# smoothieboard-5driver_2.net
KiCad netlist of a schematic drawn in Altium Designer
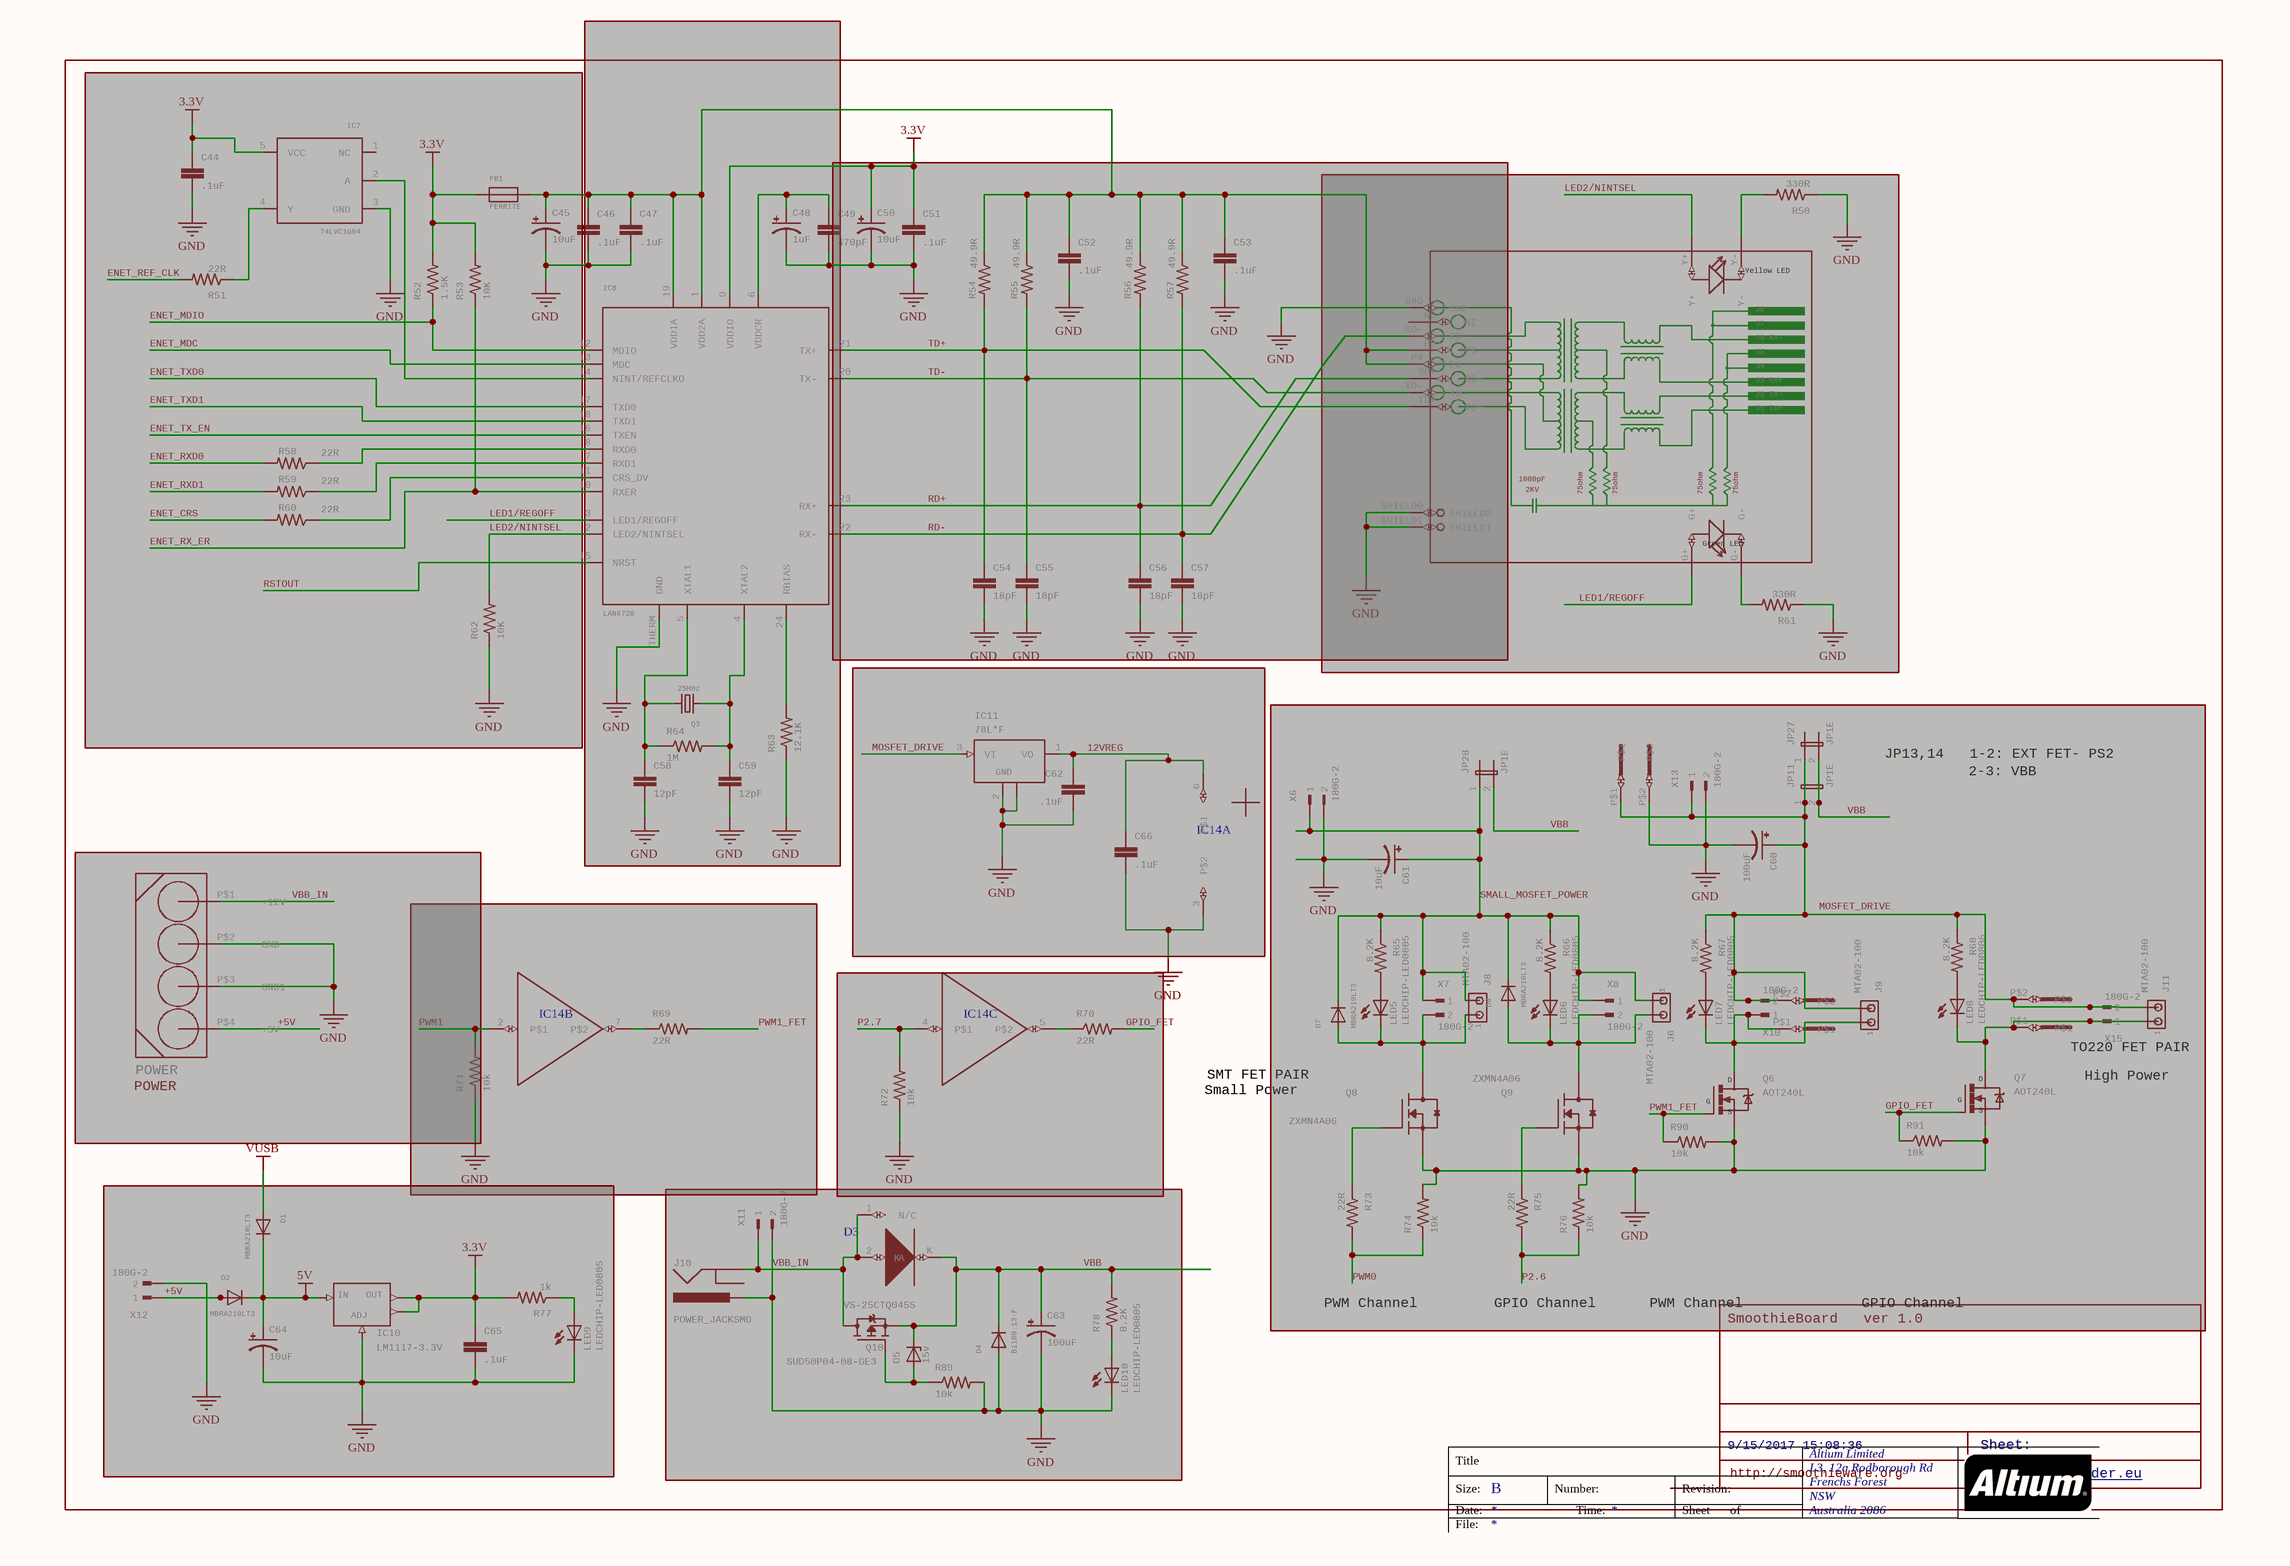
[diagram p0: smoothieboard-5driver_2.SchDoc]

(export (version "E")
  (design (tool "Eeschema 10.0.6"))
  (components
    (comp (ref "C44")
      (value ".1uF")
      (footprint "C0603")
      (description "CAPACITOR, European symbol")
      (libsource (lib "resistor") (part "C-EUC0603"))
    )
    (comp (ref "C45") (value "10uF") (footprint "EIA3216") (libsource (lib "SparkFun") (part "CAP_POL1206")))
    (comp (ref "C46")
      (value ".1uF")
      (footprint "C0603")
      (description "CAPACITOR, European symbol")
      (libsource (lib "resistor") (part "C-EUC0603"))
    )
    (comp (ref "C47")
      (value ".1uF")
      (footprint "C0603")
      (description "CAPACITOR, European symbol")
      (libsource (lib "resistor") (part "C-EUC0603"))
    )
    (comp (ref "C48") (value "1uF") (footprint "EIA3216") (libsource (lib "SparkFun") (part "CAP_POL1206")))
    (comp (ref "C49")
      (value "470pF")
      (footprint "C0603K")
      (description "CAPACITOR, European symbol")
      (libsource (lib "resistor") (part "C-EUC0603K"))
    )
    (comp (ref "C50") (value "10uF") (footprint "EIA3216") (libsource (lib "SparkFun") (part "CAP_POL1206")))
    (comp (ref "C51")
      (value ".1uF")
      (footprint "C0603")
      (description "CAPACITOR, European symbol")
      (libsource (lib "resistor") (part "C-EUC0603"))
    )
    (comp (ref "C52")
      (value ".1uF")
      (footprint "C0603")
      (description "CAPACITOR, European symbol")
      (libsource (lib "resistor") (part "C-EUC0603"))
    )
    (comp (ref "C53")
      (value ".1uF")
      (footprint "C0603")
      (description "CAPACITOR, European symbol")
      (libsource (lib "resistor") (part "C-EUC0603"))
    )
    (comp (ref "C54")
      (value "18pF")
      (footprint "C0603")
      (description "CAPACITOR, European symbol")
      (libsource (lib "resistor") (part "C-EUC0603"))
    )
    (comp (ref "C55")
      (value "18pF")
      (footprint "C0603")
      (description "CAPACITOR, European symbol")
      (libsource (lib "resistor") (part "C-EUC0603"))
    )
    (comp (ref "C56")
      (value "18pF")
      (footprint "C0603")
      (description "CAPACITOR, European symbol")
      (libsource (lib "resistor") (part "C-EUC0603"))
    )
    (comp (ref "C57")
      (value "18pF")
      (footprint "C0603")
      (description "CAPACITOR, European symbol")
      (libsource (lib "resistor") (part "C-EUC0603"))
    )
    (comp (ref "C58")
      (value "12pF")
      (footprint "C0603")
      (description "CAPACITOR, European symbol")
      (libsource (lib "resistor") (part "C-EUC0603"))
    )
    (comp (ref "C59")
      (value "12pF")
      (footprint "C0603")
      (description "CAPACITOR, European symbol")
      (libsource (lib "resistor") (part "C-EUC0603"))
    )
    (comp (ref "C60")
      (value "100uF")
      (footprint "PANASONIC_E")
      (libsource (lib "SparkFun") (part "CAP_POLE"))
    )
    (comp (ref "C61") (value "10uF") (footprint "EIA3216") (libsource (lib "") (part "CAP_POL1206_1")))
    (comp (ref "C62")
      (value ".1uF")
      (footprint "C0603")
      (description "CAPACITOR, European symbol")
      (libsource (lib "") (part "C-EUC0603_1"))
    )
    (comp (ref "C63")
      (value "100uF")
      (footprint "PANASONIC_E")
      (libsource (lib "SparkFun-Capacitors") (part "CAP_POLE"))
    )
    (comp (ref "C64") (value "10uF") (footprint "EIA3216") (libsource (lib "SparkFun") (part "CAP_POL1206")))
    (comp (ref "C65")
      (value ".1uF")
      (footprint "C0603")
      (description "CAPACITOR, European symbol")
      (libsource (lib "resistor") (part "C-EUC0603"))
    )
    (comp (ref "C66")
      (value ".1uF")
      (footprint "C0603")
      (description "CAPACITOR, European symbol")
      (libsource (lib "resistor") (part "C-EUC0603"))
    )
    (comp (ref "D1")
      (value "MBRA210LT3")
      (footprint "SMADIODE")
      (libsource (lib "microbuilder") (part "DIODESMA"))
    )
    (comp (ref "D2")
      (value "MBRA210LT3")
      (footprint "SMADIODE")
      (libsource (lib "microbuilder") (part "DIODESMA"))
    )
    (comp (ref "D3")
      (value "VS-25CTQ045S")
      (footprint "TO263AB")
      (fields (field (name "LIBRARYNAME") "Geos"))
      (libsource (lib "Geos") (part "ETH1506S"))
    )
    (comp (ref "D4")
      (value "B1100-13-F")
      (footprint "SMADIODE")
      (libsource (lib "microbuilder") (part "DIODESMA"))
    )
    (comp (ref "D5")
      (value "15v")
      (footprint "SMB")
      (description "Z-Diode")
      (libsource (lib "diode") (part "ZENER-DIODESMB"))
    )
    (comp (ref "D7")
      (value "MBRA210LT3")
      (footprint "SMADIODE")
      (libsource (lib "microbuilder") (part "DIODESMA"))
    )
    (comp (ref "D8")
      (value "MBRA210LT3")
      (footprint "SMADIODE")
      (libsource (lib "microbuilder") (part "DIODESMA"))
    )
    (comp (ref "FB1") (value "FERRITE") (footprint "0603") (libsource (lib "microbuilder") (part "FERRITE")))
    (comp (ref "IC7")
      (value "74LVC1G04")
      (footprint "SOT23-5")
      (description "74LVC1G04 - Single Inverter Gate    SOT23-5 SN74LVC1G04DBVR - Digikey: 296-11599-1-ND")
      (libsource (lib "microbuilder") (part "74LVC1G04"))
    )
    (comp (ref "IC8")
      (value "LAN8720")
      (footprint "QFN24_4MM")
      (description "LAN8720A 10/100 Ethernet PHY   Mouser: 886-LAN8720AI-CP")
      (libsource (lib "microbuilder") (part "LAN8720"))
    )
    (comp (ref "IC10")
      (value "LM1117-3.3V")
      (footprint "SOT223")
      (fields (field (name "ADJ") "ADJ") (field (name "IN") "IN") (field (name "OUT") "OUT"))
      (libsource (lib "SparkFun") (part "V_REG_LM1117SOT223"))
    )
    (comp (ref "IC11")
      (value "78L*F")
      (footprint "SOT89")
      (fields (field (name "GND") "GND"))
      (libsource (lib "linear") (part "78L*F"))
    )
    (comp (ref "IC14")
      (value "TC4427")
      (footprint "SOIC8")
      (fields (field (name "LIBRARYNAME") "custom_esorensen"))
      (libsource (lib "custom_esorensen") (part "TC4427"))
    )
    (comp (ref "J6")
      (value "MTA02-100")
      (footprint "10X02MTA")
      (description "AMP connector")
      (fields (field (name "1") "1"))
      (libsource (lib "con-amp") (part "MTA02-100"))
    )
    (comp (ref "J8")
      (value "MTA02-100")
      (footprint "10X02MTA")
      (description "AMP connector")
      (fields (field (name "1") "1"))
      (libsource (lib "con-amp") (part "MTA02-100"))
    )
    (comp (ref "J9")
      (value "MTA02-100")
      (footprint "10X02MTA")
      (description "AMP connector")
      (fields (field (name "1") "1"))
      (libsource (lib "con-amp") (part "MTA02-100"))
    )
    (comp (ref "J10")
      (value "POWER_JACKSMD")
      (footprint "POWER_JACK_SMD")
      (libsource (lib "SparkFun") (part "POWER_JACKSMD"))
    )
    (comp (ref "J11")
      (value "MTA02-100")
      (footprint "10X02MTA")
      (description "AMP connector")
      (fields (field (name "1") "1"))
      (libsource (lib "con-amp") (part "MTA02-100"))
    )
    (comp (ref "JP11")
      (value "JP1E")
      (footprint "JP1")
      (description "JUMPER")
      (libsource (lib "jumper") (part "JP1E"))
    )
    (comp (ref "JP27")
      (value "JP1E")
      (footprint "JP1")
      (description "JUMPER")
      (libsource (lib "jumper") (part "JP1E"))
    )
    (comp (ref "JP28")
      (value "JP1E")
      (footprint "JP1")
      (description "JUMPER")
      (libsource (lib "jumper") (part "JP1E"))
    )
    (comp (ref "LED5")
      (value "LEDCHIP-LED0805")
      (footprint "CHIP-LED0805")
      (libsource (lib "led") (part "LEDCHIP-LED0805"))
    )
    (comp (ref "LED6")
      (value "LEDCHIP-LED0805")
      (footprint "CHIP-LED0805")
      (libsource (lib "led") (part "LEDCHIP-LED0805"))
    )
    (comp (ref "LED7")
      (value "LEDCHIP-LED0805")
      (footprint "CHIP-LED0805")
      (libsource (lib "led") (part "LEDCHIP-LED0805"))
    )
    (comp (ref "LED8")
      (value "LEDCHIP-LED0805")
      (footprint "CHIP-LED0805")
      (libsource (lib "led") (part "LEDCHIP-LED0805"))
    )
    (comp (ref "LED9")
      (value "LEDCHIP-LED0805")
      (footprint "CHIP-LED0805")
      (libsource (lib "led") (part "LEDCHIP-LED0805"))
    )
    (comp (ref "LED10")
      (value "LEDCHIP-LED0805")
      (footprint "CHIP-LED0805")
      (libsource (lib "led") (part "LEDCHIP-LED0805"))
    )
    (comp (ref "POWER")
      (value "POWER")
      (footprint "MOLEX8981")
      (description "ATX HDD Connector 4 pin Molex8981 Connector")
      (fields (field (name "LIBRARYNAME") "Geos"))
      (libsource (lib "Geos") (part "HDD-ATX_CON"))
    )
    (comp (ref "Q3")
      (value "25MHz")
      (footprint "CRYSTAL_3.2X2.5")
      (libsource (lib "microbuilder") (part "CRYSTALTHIN"))
    )
    (comp (ref "Q6")
      (value "AOT240L")
      (footprint "TO220BV")
      (description "HEXFET Power MOSFET")
      (fields (field (name "D") "D") (field (name "S") "S") (field (name "G") "G"))
      (libsource (lib "transistor-power") (part "IRF540"))
    )
    (comp (ref "Q7")
      (value "AOT240L")
      (footprint "TO220BV")
      (description "HEXFET Power MOSFET")
      (fields (field (name "D") "D") (field (name "S") "S") (field (name "G") "G"))
      (libsource (lib "transistor-power") (part "IRF540"))
    )
    (comp (ref "Q8")
      (value "ZXMN4A06")
      (footprint "SOT230P700X160-4N")
      (fields (field (name "LIBRARYNAME") "ipc-7351-transistor"))
      (libsource (lib "ipc-7351-transistor") (part "MOSFET-NCH_SOT-223"))
    )
    (comp (ref "Q9")
      (value "ZXMN4A06")
      (footprint "SOT230P700X160-4N")
      (fields (field (name "LIBRARYNAME") "ipc-7351-transistor"))
      (libsource (lib "ipc-7351-transistor") (part "MOSFET-NCH_SOT-223"))
    )
    (comp (ref "Q10")
      (value "SUD50P04-08-GE3")
      (footprint "TO252")
      (libsource (lib "transistor-fet") (part "SPD30P06PTO252"))
    )
    (comp (ref "R50")
      (value "330R")
      (footprint "R0603")
      (description "RESISTOR, American symbol")
      (libsource (lib "resistor") (part "R-US_R0603"))
    )
    (comp (ref "R51")
      (value "22R")
      (footprint "R0603")
      (description "RESISTOR, American symbol")
      (libsource (lib "resistor") (part "R-US_R0603"))
    )
    (comp (ref "R52")
      (value "1.5K")
      (footprint "R0603")
      (description "RESISTOR, American symbol")
      (libsource (lib "resistor") (part "R-US_R0603"))
    )
    (comp (ref "R53")
      (value "10K")
      (footprint "R0603")
      (description "RESISTOR, American symbol")
      (libsource (lib "resistor") (part "R-US_R0603"))
    )
    (comp (ref "R54")
      (value "49.9R")
      (footprint "R0603")
      (description "RESISTOR, American symbol")
      (libsource (lib "resistor") (part "R-US_R0603"))
    )
    (comp (ref "R55")
      (value "49.9R")
      (footprint "R0603")
      (description "RESISTOR, American symbol")
      (libsource (lib "resistor") (part "R-US_R0603"))
    )
    (comp (ref "R56")
      (value "49.9R")
      (footprint "R0603")
      (description "RESISTOR, American symbol")
      (libsource (lib "resistor") (part "R-US_R0603"))
    )
    (comp (ref "R57")
      (value "49.9R")
      (footprint "R0603")
      (description "RESISTOR, American symbol")
      (libsource (lib "resistor") (part "R-US_R0603"))
    )
    (comp (ref "R58")
      (value "22R")
      (footprint "R0603")
      (description "RESISTOR, American symbol")
      (libsource (lib "resistor") (part "R-US_R0603"))
    )
    (comp (ref "R59")
      (value "22R")
      (footprint "R0603")
      (description "RESISTOR, American symbol")
      (libsource (lib "resistor") (part "R-US_R0603"))
    )
    (comp (ref "R60")
      (value "22R")
      (footprint "R0603")
      (description "RESISTOR, American symbol")
      (libsource (lib "resistor") (part "R-US_R0603"))
    )
    (comp (ref "R61")
      (value "330R")
      (footprint "R0603")
      (description "RESISTOR, American symbol")
      (libsource (lib "resistor") (part "R-US_R0603"))
    )
    (comp (ref "R62")
      (value "10K")
      (footprint "R0603")
      (description "RESISTOR, American symbol")
      (libsource (lib "resistor") (part "R-US_R0603"))
    )
    (comp (ref "R63")
      (value "12.1K")
      (footprint "R0603")
      (description "RESISTOR, American symbol")
      (libsource (lib "resistor") (part "R-US_R0603"))
    )
    (comp (ref "R64")
      (value "1M")
      (footprint "R0603")
      (description "RESISTOR, American symbol")
      (libsource (lib "resistor") (part "R-US_R0603"))
    )
    (comp (ref "R65")
      (value "8.2K")
      (footprint "R0603")
      (description "RESISTOR, American symbol")
      (libsource (lib "resistor") (part "R-US_R0603"))
    )
    (comp (ref "R66")
      (value "8.2K")
      (footprint "R0603")
      (description "RESISTOR, American symbol")
      (libsource (lib "resistor") (part "R-US_R0603"))
    )
    (comp (ref "R67")
      (value "8.2K")
      (footprint "R0603")
      (description "RESISTOR, American symbol")
      (libsource (lib "resistor") (part "R-US_R0603"))
    )
    (comp (ref "R68")
      (value "8.2K")
      (footprint "R0603")
      (description "RESISTOR, American symbol")
      (libsource (lib "resistor") (part "R-US_R0603"))
    )
    (comp (ref "R69")
      (value "22R")
      (footprint "R0603")
      (description "RESISTOR, American symbol")
      (libsource (lib "resistor") (part "R-US_R0603"))
    )
    (comp (ref "R70")
      (value "22R")
      (footprint "R0603")
      (description "RESISTOR, American symbol")
      (libsource (lib "resistor") (part "R-US_R0603"))
    )
    (comp (ref "R71")
      (value "10k")
      (footprint "R0603")
      (description "RESISTOR, American symbol")
      (libsource (lib "resistor") (part "R-US_R0603"))
    )
    (comp (ref "R72")
      (value "10k")
      (footprint "R0603")
      (description "RESISTOR, American symbol")
      (libsource (lib "resistor") (part "R-US_R0603"))
    )
    (comp (ref "R73")
      (value "22R")
      (footprint "R0603")
      (description "RESISTOR, American symbol")
      (libsource (lib "resistor") (part "R-US_R0603"))
    )
    (comp (ref "R74")
      (value "10k")
      (footprint "R0603")
      (description "RESISTOR, American symbol")
      (libsource (lib "resistor") (part "R-US_R0603"))
    )
    (comp (ref "R75")
      (value "22R")
      (footprint "R0603")
      (description "RESISTOR, American symbol")
      (libsource (lib "resistor") (part "R-US_R0603"))
    )
    (comp (ref "R76")
      (value "10k")
      (footprint "R0603")
      (description "RESISTOR, American symbol")
      (libsource (lib "resistor") (part "R-US_R0603"))
    )
    (comp (ref "R77")
      (value "1k")
      (footprint "R0603")
      (description "RESISTOR, American symbol")
      (libsource (lib "resistor") (part "R-US_R0603"))
    )
    (comp (ref "R78")
      (value "8.2K")
      (footprint "R0603")
      (description "RESISTOR, American symbol")
      (libsource (lib "resistor") (part "R-US_R0603"))
    )
    (comp (ref "R89")
      (value "10k")
      (footprint "R0603")
      (description "RESISTOR, American symbol")
      (libsource (lib "resistor") (part "R-US_R0603"))
    )
    (comp (ref "R90")
      (value "10k")
      (footprint "R0603")
      (description "RESISTOR, American symbol")
      (libsource (lib "resistor") (part "R-US_R0603"))
    )
    (comp (ref "R91")
      (value "10k")
      (footprint "R0603")
      (description "RESISTOR, American symbol")
      (libsource (lib "resistor") (part "R-US_R0603"))
    )
    (comp (ref "RJ1")
      (value "HR911105A")
      (footprint "HR911105A")
      (description "SOC006")
      (fields
        (field (name "J8") "J8")
        (field (name "J7") "J7")
        (field (name "J6RX-") "J6 RX-")
        (field (name "J5") "J5")
        (field (name "J4") "J4")
        (field (name "J3RX+") "J3 RX+")
        (field (name "J2TX-") "J2 TX-")
        (field (name "J1TX+") "J1 TX+")
        (field (name "YELLOWLED") "Yellow LED")
        (field (name "GREENLED") "Green LED")
        (field (name "75OHM") "75ohm")
        (field (name "75OHM_1") "75ohm")
        (field (name "75OHM_2") "75ohm")
        (field (name "75OHM_3") "75ohm")
        (field (name "1000PF") "1000pF")
        (field (name "2KV") "2KV")
        (field (name "LIBRARYNAME") "Itead_BP_110825.lbr")
      )
      (libsource (lib "Itead_BP_110825.lbr") (part "HR911105A"))
    )
    (comp (ref "U$5")
      (value "5MMCONN")
      (footprint "1715250000")
      (fields (field (name "LIBRARYNAME") "eric_sorensen"))
      (libsource (lib "eric_sorensen") (part "5MMCONN"))
    )
    (comp (ref "U$6")
      (value "5MMCONN")
      (footprint "1715250000")
      (fields (field (name "LIBRARYNAME") "eric_sorensen"))
      (libsource (lib "eric_sorensen") (part "5MMCONN"))
    )
    (comp (ref "U$10")
      (value "5MMCONN")
      (footprint "1715250000")
      (fields (field (name "LIBRARYNAME") "eric_sorensen"))
      (libsource (lib "eric_sorensen") (part "5MMCONN"))
    )
    (comp (ref "X6")
      (value "180G-2")
      (footprint "180G-2")
      (description "WEIDMUELLER CLAMP CONNECTOR")
      (fields (field (name "MF") "MF") (field (name "MPN") "MPN"))
      (libsource (lib "con-weidmueller-sl35") (part "180G-2"))
    )
    (comp (ref "X7")
      (value "180G-2")
      (footprint "180G-2")
      (description "WEIDMUELLER CLAMP CONNECTOR")
      (fields (field (name "MF") "MF") (field (name "MPN") "MPN"))
      (libsource (lib "") (part "180G-2_1"))
    )
    (comp (ref "X8")
      (value "180G-2")
      (footprint "180G-2")
      (description "WEIDMUELLER CLAMP CONNECTOR")
      (fields (field (name "MF") "MF") (field (name "MPN") "MPN"))
      (libsource (lib "") (part "180G-2_1"))
    )
    (comp (ref "X10")
      (value "180G-2")
      (footprint "180G-2")
      (description "WEIDMUELLER CLAMP CONNECTOR")
      (fields (field (name "MF") "MF") (field (name "MPN") "MPN"))
      (libsource (lib "con-weidmueller-sl35") (part "180G-2"))
    )
    (comp (ref "X11")
      (value "180G-2")
      (footprint "180G-2")
      (description "WEIDMUELLER CLAMP CONNECTOR")
      (fields (field (name "MF") "MF") (field (name "MPN") "MPN"))
      (libsource (lib "con-weidmueller-sl35") (part "180G-2"))
    )
    (comp (ref "X12")
      (value "180G-2")
      (footprint "180G-2")
      (description "WEIDMUELLER CLAMP CONNECTOR")
      (fields (field (name "MF") "MF") (field (name "MPN") "MPN"))
      (libsource (lib "") (part "180G-2_2"))
    )
    (comp (ref "X13")
      (value "180G-2")
      (footprint "180G-2")
      (description "WEIDMUELLER CLAMP CONNECTOR")
      (fields (field (name "MF") "MF") (field (name "MPN") "MPN"))
      (libsource (lib "con-weidmueller-sl35") (part "180G-2"))
    )
    (comp (ref "X15")
      (value "180G-2")
      (footprint "180G-2")
      (description "WEIDMUELLER CLAMP CONNECTOR")
      (fields (field (name "MF") "MF") (field (name "MPN") "MPN"))
      (libsource (lib "con-weidmueller-sl35") (part "180G-2"))
    )
  )
  (nets
    (net (code "1") (name "/+5V") (class "Default")
      (node (ref "D2") (pin "A") (pinfunction "A_A") (pintype "passive"))
      (node (ref "POWER") (pin "P$4") (pinfunction "+5V_P$4") (pintype "power_in"))
      (node (ref "X12") (pin "1") (pinfunction "1_1") (pintype "passive"))
    )
    (net (code "3") (name "/12VREG") (class "Default")
      (node (ref "C62") (pin "1") (pinfunction "1_1") (pintype "passive"))
      (node (ref "C66") (pin "1") (pinfunction "1_1") (pintype "passive"))
      (node (ref "IC11") (pin "1") (pinfunction "VO_1") (pintype "passive"))
      (node (ref "IC14") (pin "6") (pinfunction "P$1_6") (pintype "bidirectional"))
    )
    (net (code "4") (name "/ENET_CRS") (class "Default")
      (node (ref "R60") (pin "2") (pinfunction "2_2") (pintype "passive"))
    )
    (net (code "5") (name "/ENET_MDC") (class "Default")
      (node (ref "IC8") (pin "13") (pinfunction "MDC_13") (pintype "bidirectional"))
    )
    (net (code "6") (name "/ENET_MDIO") (class "Default")
      (node (ref "IC8") (pin "12") (pinfunction "MDIO_12") (pintype "bidirectional"))
      (node (ref "R52") (pin "1") (pinfunction "1_1") (pintype "passive"))
    )
    (net (code "7") (name "/ENET_REF_CLK") (class "Default")
      (node (ref "R51") (pin "2") (pinfunction "2_2") (pintype "passive"))
    )
    (net (code "8") (name "/ENET_RXD0") (class "Default")
      (node (ref "R58") (pin "2") (pinfunction "2_2") (pintype "passive"))
    )
    (net (code "9") (name "/ENET_RXD1") (class "Default")
      (node (ref "R59") (pin "2") (pinfunction "2_2") (pintype "passive"))
    )
    (net (code "10") (name "/ENET_RX_ER") (class "Default")
      (node (ref "IC8") (pin "10") (pinfunction "RXER_10") (pintype "bidirectional"))
      (node (ref "R53") (pin "1") (pinfunction "1_1") (pintype "passive"))
    )
    (net (code "11") (name "/ENET_TXD0") (class "Default")
      (node (ref "IC8") (pin "17") (pinfunction "TXD0_17") (pintype "bidirectional"))
    )
    (net (code "12") (name "/ENET_TXD1") (class "Default")
      (node (ref "IC8") (pin "18") (pinfunction "TXD1_18") (pintype "bidirectional"))
    )
    (net (code "13") (name "/ENET_TX_EN") (class "Default")
      (node (ref "IC8") (pin "16") (pinfunction "TXEN_16") (pintype "bidirectional"))
    )
    (net (code "14") (name "/GPIO_FET") (class "Default")
      (node (ref "Q7") (pin "G") (pinfunction "G_G") (pintype "passive"))
      (node (ref "R70") (pin "2") (pinfunction "2_2") (pintype "passive"))
      (node (ref "R91") (pin "1") (pinfunction "1_1") (pintype "passive"))
    )
    (net (code "15") (name "/LED1{slash}REGOFF") (class "Default")
      (node (ref "IC8") (pin "3") (pinfunction "LED1/REGOFF_3") (pintype "bidirectional"))
      (node (ref "RJ1") (pin "G+") (pinfunction "G+_G+") (pintype "bidirectional"))
    )
    (net (code "16") (name "/LED2{slash}NINTSEL") (class "Default")
      (node (ref "IC8") (pin "2") (pinfunction "LED2/NINTSEL_2") (pintype "bidirectional"))
      (node (ref "R62") (pin "2") (pinfunction "2_2") (pintype "passive"))
      (node (ref "RJ1") (pin "Y+") (pinfunction "Y+_Y+") (pintype "bidirectional"))
    )
    (net (code "17") (name "/MOSFET_DRIVE") (class "Default")
      (node (ref "IC11") (pin "3") (pinfunction "VI_3") (pintype "input"))
    )
    (net (code "18") (name "/P2.6") (class "Default")
      (node (ref "R75") (pin "2") (pinfunction "2_2") (pintype "passive"))
      (node (ref "R76") (pin "1") (pinfunction "1_1") (pintype "passive"))
    )
    (net (code "19") (name "/P2.7") (class "Default")
      (node (ref "IC14") (pin "4") (pinfunction "P$1_4") (pintype "bidirectional"))
      (node (ref "R72") (pin "2") (pinfunction "2_2") (pintype "passive"))
    )
    (net (code "20") (name "/PWM0") (class "Default")
      (node (ref "R73") (pin "2") (pinfunction "2_2") (pintype "passive"))
      (node (ref "R74") (pin "1") (pinfunction "1_1") (pintype "passive"))
    )
    (net (code "21") (name "/PWM1") (class "Default")
      (node (ref "IC14") (pin "2") (pinfunction "P$1_2") (pintype "bidirectional"))
      (node (ref "R71") (pin "2") (pinfunction "2_2") (pintype "passive"))
    )
    (net (code "22") (name "/PWM1_FET") (class "Default")
      (node (ref "Q6") (pin "G") (pinfunction "G_G") (pintype "passive"))
      (node (ref "R69") (pin "2") (pinfunction "2_2") (pintype "passive"))
      (node (ref "R90") (pin "1") (pinfunction "1_1") (pintype "passive"))
    )
    (net (code "23") (name "/RD+") (class "Default")
      (node (ref "C56") (pin "1") (pinfunction "1_1") (pintype "passive"))
      (node (ref "IC8") (pin "23") (pinfunction "RX+_23") (pintype "bidirectional"))
      (node (ref "R56") (pin "2") (pinfunction "2_2") (pintype "passive"))
      (node (ref "RJ1") (pin "RD+") (pinfunction "RD+_RD+") (pintype "bidirectional"))
    )
    (net (code "24") (name "/RD-") (class "Default")
      (node (ref "C57") (pin "1") (pinfunction "1_1") (pintype "passive"))
      (node (ref "IC8") (pin "22") (pinfunction "RX-_22") (pintype "bidirectional"))
      (node (ref "R57") (pin "2") (pinfunction "2_2") (pintype "passive"))
      (node (ref "RJ1") (pin "RD-") (pinfunction "RD-_RD-") (pintype "bidirectional"))
    )
    (net (code "25") (name "/RSTOUT") (class "Default")
      (node (ref "IC8") (pin "15") (pinfunction "NRST_15") (pintype "bidirectional"))
    )
    (net (code "26") (name "/SMALL_MOSFET_POWER") (class "Default")
      (node (ref "C61") (pin "A") (pinfunction "+_A") (pintype "passive"))
      (node (ref "D7") (pin "C") (pinfunction "C_C") (pintype "passive"))
      (node (ref "D8") (pin "C") (pinfunction "C_C") (pintype "passive"))
      (node (ref "J6") (pin "1") (pinfunction "1_1") (pintype "passive"))
      (node (ref "J8") (pin "2") (pinfunction "2_2") (pintype "passive"))
      (node (ref "JP28") (pin "1") (pinfunction "1_1") (pintype "passive"))
      (node (ref "R65") (pin "1") (pinfunction "1_1") (pintype "passive"))
      (node (ref "R66") (pin "1") (pinfunction "1_1") (pintype "passive"))
      (node (ref "X6") (pin "1") (pinfunction "1_1") (pintype "passive"))
      (node (ref "X7") (pin "1") (pinfunction "1_1") (pintype "passive"))
      (node (ref "X8") (pin "1") (pinfunction "1_1") (pintype "passive"))
    )
    (net (code "27") (name "/TD+") (class "Default")
      (node (ref "C54") (pin "1") (pinfunction "1_1") (pintype "passive"))
      (node (ref "IC8") (pin "21") (pinfunction "TX+_21") (pintype "bidirectional"))
      (node (ref "R54") (pin "2") (pinfunction "2_2") (pintype "passive"))
      (node (ref "RJ1") (pin "TD+") (pinfunction "TD+_TD+") (pintype "bidirectional"))
    )
    (net (code "28") (name "/TD-") (class "Default")
      (node (ref "C55") (pin "1") (pinfunction "1_1") (pintype "passive"))
      (node (ref "IC8") (pin "20") (pinfunction "TX-_20") (pintype "bidirectional"))
      (node (ref "R55") (pin "2") (pinfunction "2_2") (pintype "passive"))
      (node (ref "RJ1") (pin "TD-") (pinfunction "TD-_TD-") (pintype "bidirectional"))
    )
    (net (code "29") (name "/VBB") (class "Default")
      (node (ref "C63") (pin "+") (pinfunction "+_+") (pintype "passive"))
      (node (ref "D3") (pin "K") (pinfunction "K_K") (pintype "bidirectional"))
      (node (ref "D4") (pin "C") (pinfunction "C_C") (pintype "passive"))
      (node (ref "D5") (pin "C") (pinfunction "C_C") (pintype "passive"))
      (node (ref "JP11") (pin "2") (pinfunction "2_2") (pintype "passive"))
      (node (ref "JP27") (pin "2") (pinfunction "2_2") (pintype "passive"))
      (node (ref "JP28") (pin "2") (pinfunction "2_2") (pintype "passive"))
      (node (ref "Q10") (pin "2") (pinfunction "S_2") (pintype "passive"))
      (node (ref "R78") (pin "2") (pinfunction "2_2") (pintype "passive"))
    )
    (net (code "30") (name "3.3V") (class "Default")
      (node (ref "C44") (pin "1") (pinfunction "1_1") (pintype "passive"))
      (node (ref "C50") (pin "A") (pinfunction "+_A") (pintype "passive"))
      (node (ref "C51") (pin "1") (pinfunction "1_1") (pintype "passive"))
      (node (ref "C65") (pin "1") (pinfunction "1_1") (pintype "passive"))
      (node (ref "FB1") (pin "1") (pinfunction "P$1_1") (pintype "bidirectional"))
      (node (ref "IC10") (pin "2") (pinfunction "OUT_2") (pintype "output"))
      (node (ref "IC10") (pin "4") (pinfunction "OUT_4") (pintype "output"))
      (node (ref "IC7") (pin "5") (pinfunction "VCC_5") (pintype "power_in"))
      (node (ref "IC8") (pin "9") (pinfunction "VDDIO_9") (pintype "bidirectional"))
      (node (ref "R52") (pin "2") (pinfunction "2_2") (pintype "passive"))
      (node (ref "R53") (pin "2") (pinfunction "2_2") (pintype "passive"))
      (node (ref "R77") (pin "2") (pinfunction "2_2") (pintype "passive"))
    )
    (net (code "31") (name "5V") (class "Default")
      (node (ref "C64") (pin "A") (pinfunction "+_A") (pintype "passive"))
      (node (ref "D1") (pin "C") (pinfunction "C_C") (pintype "passive"))
      (node (ref "D2") (pin "C") (pinfunction "C_C") (pintype "passive"))
      (node (ref "IC10") (pin "3") (pinfunction "IN_3") (pintype "input"))
    )
    (net (code "32") (name "GND") (class "Default")
      (node (ref "C44") (pin "2") (pinfunction "2_2") (pintype "passive"))
      (node (ref "C45") (pin "C") (pinfunction "-_C") (pintype "passive"))
      (node (ref "C46") (pin "2") (pinfunction "2_2") (pintype "passive"))
      (node (ref "C47") (pin "2") (pinfunction "2_2") (pintype "passive"))
      (node (ref "C48") (pin "C") (pinfunction "-_C") (pintype "passive"))
      (node (ref "C49") (pin "2") (pinfunction "2_2") (pintype "passive"))
      (node (ref "C50") (pin "C") (pinfunction "-_C") (pintype "passive"))
      (node (ref "C51") (pin "2") (pinfunction "2_2") (pintype "passive"))
      (node (ref "C52") (pin "2") (pinfunction "2_2") (pintype "passive"))
      (node (ref "C53") (pin "2") (pinfunction "2_2") (pintype "passive"))
      (node (ref "C54") (pin "2") (pinfunction "2_2") (pintype "passive"))
      (node (ref "C55") (pin "2") (pinfunction "2_2") (pintype "passive"))
      (node (ref "C56") (pin "2") (pinfunction "2_2") (pintype "passive"))
      (node (ref "C57") (pin "2") (pinfunction "2_2") (pintype "passive"))
      (node (ref "C58") (pin "2") (pinfunction "2_2") (pintype "passive"))
      (node (ref "C59") (pin "2") (pinfunction "2_2") (pintype "passive"))
      (node (ref "C60") (pin "-") (pinfunction "-_-") (pintype "passive"))
      (node (ref "C61") (pin "C") (pinfunction "-_C") (pintype "passive"))
      (node (ref "C62") (pin "2") (pinfunction "2_2") (pintype "passive"))
      (node (ref "C63") (pin "-") (pinfunction "-_-") (pintype "passive"))
      (node (ref "C64") (pin "C") (pinfunction "-_C") (pintype "passive"))
      (node (ref "C65") (pin "2") (pinfunction "2_2") (pintype "passive"))
      (node (ref "C66") (pin "2") (pinfunction "2_2") (pintype "passive"))
      (node (ref "D3") (pin "1") (pinfunction "N/C_1") (pintype "bidirectional"))
      (node (ref "D3") (pin "2") (pinfunction "A_2") (pintype "bidirectional"))
      (node (ref "D4") (pin "A") (pinfunction "A_A") (pintype "passive"))
      (node (ref "IC10") (pin "1") (pinfunction "ADJ_1") (pintype "input"))
      (node (ref "IC11") (pin "2") (pinfunction "GND_2") (pintype "passive"))
      (node (ref "IC11") (pin "2@1") (pinfunction "GND_2@1") (pintype "passive"))
      (node (ref "IC14") (pin "3") (pinfunction "P$2_3") (pintype "bidirectional"))
      (node (ref "IC7") (pin "3") (pinfunction "GND_3") (pintype "power_in"))
      (node (ref "IC8") (pin "THERM") (pinfunction "GND_THERM") (pintype "bidirectional"))
      (node (ref "J10") (pin "P$4") (pinfunction "GND_P$4") (pintype "bidirectional"))
      (node (ref "J10") (pin "VIN0") (pinfunction "PWR_VIN0") (pintype "bidirectional"))
      (node (ref "LED10") (pin "C") (pinfunction "C_C") (pintype "passive"))
      (node (ref "LED9") (pin "C") (pinfunction "C_C") (pintype "passive"))
      (node (ref "POWER") (pin "P$1") (pinfunction "+12V_P$1") (pintype "power_in"))
      (node (ref "POWER") (pin "P$2") (pinfunction "GND_P$2") (pintype "power_in"))
      (node (ref "POWER") (pin "P$3") (pinfunction "GND1_P$3") (pintype "power_in"))
      (node (ref "Q10") (pin "3") (pinfunction "D_3") (pintype "passive"))
      (node (ref "Q6") (pin "S") (pinfunction "S_S") (pintype "passive"))
      (node (ref "Q7") (pin "S") (pinfunction "S_S") (pintype "passive"))
      (node (ref "Q8") (pin "3") (pinfunction "S_3") (pintype "passive"))
      (node (ref "Q9") (pin "3") (pinfunction "S_3") (pintype "passive"))
      (node (ref "R50") (pin "1") (pinfunction "1_1") (pintype "passive"))
      (node (ref "R61") (pin "1") (pinfunction "1_1") (pintype "passive"))
      (node (ref "R62") (pin "1") (pinfunction "1_1") (pintype "passive"))
      (node (ref "R63") (pin "1") (pinfunction "1_1") (pintype "passive"))
      (node (ref "R71") (pin "1") (pinfunction "1_1") (pintype "passive"))
      (node (ref "R72") (pin "1") (pinfunction "1_1") (pintype "passive"))
      (node (ref "R74") (pin "2") (pinfunction "2_2") (pintype "passive"))
      (node (ref "R76") (pin "2") (pinfunction "2_2") (pintype "passive"))
      (node (ref "R89") (pin "2") (pinfunction "2_2") (pintype "passive"))
      (node (ref "R90") (pin "2") (pinfunction "2_2") (pintype "passive"))
      (node (ref "R91") (pin "2") (pinfunction "2_2") (pintype "passive"))
      (node (ref "RJ1") (pin "GND") (pinfunction "GND_GND") (pintype "bidirectional"))
      (node (ref "RJ1") (pin "SHIELD0") (pinfunction "SHIELD0_SHIELD0") (pintype "bidirectional"))
      (node (ref "RJ1") (pin "SHIELD1") (pinfunction "SHIELD1_SHIELD1") (pintype "bidirectional"))
      (node (ref "U$5") (pin "P$2") (pinfunction "P$2_P$2") (pintype "bidirectional"))
      (node (ref "X11") (pin "1") (pinfunction "1_1") (pintype "passive"))
      (node (ref "X11") (pin "2") (pinfunction "2_2") (pintype "passive"))
      (node (ref "X12") (pin "2") (pinfunction "2_2") (pintype "passive"))
      (node (ref "X13") (pin "2") (pinfunction "2_2") (pintype "passive"))
      (node (ref "X6") (pin "2") (pinfunction "2_2") (pintype "passive"))
    )
    (net (code "33") (name "Net-(C45-+)") (class "Default")
      (node (ref "C45") (pin "A") (pinfunction "+_A") (pintype "passive"))
      (node (ref "C46") (pin "1") (pinfunction "1_1") (pintype "passive"))
      (node (ref "C47") (pin "1") (pinfunction "1_1") (pintype "passive"))
      (node (ref "C52") (pin "1") (pinfunction "1_1") (pintype "passive"))
      (node (ref "C53") (pin "1") (pinfunction "1_1") (pintype "passive"))
      (node (ref "FB1") (pin "2") (pinfunction "P$2_2") (pintype "bidirectional"))
      (node (ref "IC8") (pin "1") (pinfunction "VDD2A_1") (pintype "bidirectional"))
      (node (ref "IC8") (pin "19") (pinfunction "VDD1A_19") (pintype "bidirectional"))
      (node (ref "R54") (pin "1") (pinfunction "1_1") (pintype "passive"))
      (node (ref "R55") (pin "1") (pinfunction "1_1") (pintype "passive"))
      (node (ref "R56") (pin "1") (pinfunction "1_1") (pintype "passive"))
      (node (ref "R57") (pin "1") (pinfunction "1_1") (pintype "passive"))
      (node (ref "RJ1") (pin "P4") (pinfunction "P4_P4") (pintype "bidirectional"))
      (node (ref "RJ1") (pin "P5") (pinfunction "P5_P5") (pintype "bidirectional"))
    )
    (net (code "34") (name "Net-(C48-+)") (class "Default")
      (node (ref "C48") (pin "A") (pinfunction "+_A") (pintype "passive"))
      (node (ref "C49") (pin "1") (pinfunction "1_1") (pintype "passive"))
      (node (ref "IC8") (pin "6") (pinfunction "VDDCR_6") (pintype "bidirectional"))
    )
    (net (code "35") (name "Net-(C60-Pad+)") (class "Default")
      (node (ref "C60") (pin "+") (pinfunction "+_+") (pintype "passive"))
      (node (ref "J11") (pin "2") (pinfunction "2_2") (pintype "passive"))
      (node (ref "J9") (pin "2") (pinfunction "2_2") (pintype "passive"))
      (node (ref "JP11") (pin "1") (pinfunction "1_1") (pintype "passive"))
      (node (ref "JP27") (pin "1") (pinfunction "1_1") (pintype "passive"))
      (node (ref "R67") (pin "1") (pinfunction "1_1") (pintype "passive"))
      (node (ref "R68") (pin "1") (pinfunction "1_1") (pintype "passive"))
      (node (ref "U$10") (pin "P$2") (pinfunction "P$2_P$2") (pintype "bidirectional"))
      (node (ref "U$5") (pin "P$1") (pinfunction "P$1_P$1") (pintype "bidirectional"))
      (node (ref "U$6") (pin "P$2") (pinfunction "P$2_P$2") (pintype "bidirectional"))
      (node (ref "X10") (pin "2") (pinfunction "2_2") (pintype "passive"))
      (node (ref "X13") (pin "1") (pinfunction "1_1") (pintype "passive"))
      (node (ref "X15") (pin "2") (pinfunction "2_2") (pintype "passive"))
    )
    (net (code "36") (name "Net-(IC7-A)") (class "Default")
      (node (ref "IC7") (pin "2") (pinfunction "A_2") (pintype "bidirectional"))
      (node (ref "IC8") (pin "14") (pinfunction "NINT/REFCLKO_14") (pintype "bidirectional"))
    )
    (net (code "37") (name "Net-(IC7-Y)") (class "Default")
      (node (ref "IC7") (pin "4") (pinfunction "Y_4") (pintype "bidirectional"))
      (node (ref "R51") (pin "1") (pinfunction "1_1") (pintype "passive"))
    )
    (net (code "38") (name "Net-(IC8-CRS_DV)") (class "Default")
      (node (ref "IC8") (pin "11") (pinfunction "CRS_DV_11") (pintype "bidirectional"))
      (node (ref "R60") (pin "1") (pinfunction "1_1") (pintype "passive"))
    )
    (net (code "39") (name "Net-(IC8-RBIAS)") (class "Default")
      (node (ref "IC8") (pin "24") (pinfunction "RBIAS_24") (pintype "bidirectional"))
      (node (ref "R63") (pin "2") (pinfunction "2_2") (pintype "passive"))
    )
    (net (code "40") (name "Net-(IC8-RXD0)") (class "Default")
      (node (ref "IC8") (pin "8") (pinfunction "RXD0_8") (pintype "bidirectional"))
      (node (ref "R58") (pin "1") (pinfunction "1_1") (pintype "passive"))
    )
    (net (code "41") (name "Net-(IC8-RXD1)") (class "Default")
      (node (ref "IC8") (pin "7") (pinfunction "RXD1_7") (pintype "bidirectional"))
      (node (ref "R59") (pin "1") (pinfunction "1_1") (pintype "passive"))
    )
    (net (code "42") (name "Net-(IC8-XTAL1)") (class "Default")
      (node (ref "C58") (pin "1") (pinfunction "1_1") (pintype "passive"))
      (node (ref "IC8") (pin "5") (pinfunction "XTAL1_5") (pintype "bidirectional"))
      (node (ref "Q3") (pin "2") (pinfunction "2_2") (pintype "passive"))
      (node (ref "R64") (pin "1") (pinfunction "1_1") (pintype "passive"))
    )
    (net (code "43") (name "Net-(IC8-XTAL2)") (class "Default")
      (node (ref "C59") (pin "1") (pinfunction "1_1") (pintype "passive"))
      (node (ref "IC8") (pin "4") (pinfunction "XTAL2_4") (pintype "bidirectional"))
      (node (ref "Q3") (pin "1") (pinfunction "1_1") (pintype "passive"))
      (node (ref "R64") (pin "2") (pinfunction "2_2") (pintype "passive"))
    )
    (net (code "44") (name "Net-(IC14B-P$2)") (class "Default")
      (node (ref "IC14") (pin "7") (pinfunction "P$2_7") (pintype "bidirectional"))
      (node (ref "R69") (pin "1") (pinfunction "1_1") (pintype "passive"))
    )
    (net (code "45") (name "Net-(IC14C-P$2)") (class "Default")
      (node (ref "IC14") (pin "5") (pinfunction "P$2_5") (pintype "bidirectional"))
      (node (ref "R70") (pin "1") (pinfunction "1_1") (pintype "passive"))
    )
    (net (code "46") (name "Net-(J9-Pad1)") (class "Default")
      (node (ref "J9") (pin "1") (pinfunction "1_1") (pintype "passive"))
      (node (ref "LED7") (pin "C") (pinfunction "C_C") (pintype "passive"))
      (node (ref "Q6") (pin "D") (pinfunction "D_D") (pintype "passive"))
      (node (ref "U$10") (pin "P$1") (pinfunction "P$1_P$1") (pintype "bidirectional"))
      (node (ref "X10") (pin "1") (pinfunction "1_1") (pintype "passive"))
    )
    (net (code "47") (name "Net-(J11-Pad1)") (class "Default")
      (node (ref "J11") (pin "1") (pinfunction "1_1") (pintype "passive"))
      (node (ref "LED8") (pin "C") (pinfunction "C_C") (pintype "passive"))
      (node (ref "Q7") (pin "D") (pinfunction "D_D") (pintype "passive"))
      (node (ref "U$6") (pin "P$1") (pinfunction "P$1_P$1") (pintype "bidirectional"))
      (node (ref "X15") (pin "1") (pinfunction "1_1") (pintype "passive"))
    )
    (net (code "48") (name "Net-(LED5-PadA)") (class "Default")
      (node (ref "LED5") (pin "A") (pinfunction "A_A") (pintype "passive"))
      (node (ref "R65") (pin "2") (pinfunction "2_2") (pintype "passive"))
    )
    (net (code "49") (name "Net-(LED6-PadA)") (class "Default")
      (node (ref "LED6") (pin "A") (pinfunction "A_A") (pintype "passive"))
      (node (ref "R66") (pin "2") (pinfunction "2_2") (pintype "passive"))
    )
    (net (code "50") (name "Net-(LED7-PadA)") (class "Default")
      (node (ref "LED7") (pin "A") (pinfunction "A_A") (pintype "passive"))
      (node (ref "R67") (pin "2") (pinfunction "2_2") (pintype "passive"))
    )
    (net (code "51") (name "Net-(LED8-PadA)") (class "Default")
      (node (ref "LED8") (pin "A") (pinfunction "A_A") (pintype "passive"))
      (node (ref "R68") (pin "2") (pinfunction "2_2") (pintype "passive"))
    )
    (net (code "52") (name "Net-(LED9-PadA)") (class "Default")
      (node (ref "LED9") (pin "A") (pinfunction "A_A") (pintype "passive"))
      (node (ref "R77") (pin "1") (pinfunction "1_1") (pintype "passive"))
    )
    (net (code "53") (name "Net-(LED10-PadA)") (class "Default")
      (node (ref "LED10") (pin "A") (pinfunction "A_A") (pintype "passive"))
      (node (ref "R78") (pin "1") (pinfunction "1_1") (pintype "passive"))
    )
    (net (code "54") (name "Net-(Q8-D)") (class "Default")
      (node (ref "D7") (pin "A") (pinfunction "A_A") (pintype "passive"))
      (node (ref "J8") (pin "1") (pinfunction "1_1") (pintype "passive"))
      (node (ref "LED5") (pin "C") (pinfunction "C_C") (pintype "passive"))
      (node (ref "Q8") (pin "4") (pinfunction "D_4") (pintype "passive"))
      (node (ref "X7") (pin "2") (pinfunction "2_2") (pintype "passive"))
    )
    (net (code "55") (name "Net-(Q8-G)") (class "Default")
      (node (ref "Q8") (pin "1") (pinfunction "G_1") (pintype "passive"))
      (node (ref "R73") (pin "1") (pinfunction "1_1") (pintype "passive"))
    )
    (net (code "56") (name "Net-(Q9-D)") (class "Default")
      (node (ref "D8") (pin "A") (pinfunction "A_A") (pintype "passive"))
      (node (ref "J6") (pin "2") (pinfunction "2_2") (pintype "passive"))
      (node (ref "LED6") (pin "C") (pinfunction "C_C") (pintype "passive"))
      (node (ref "Q9") (pin "4") (pinfunction "D_4") (pintype "passive"))
      (node (ref "X8") (pin "2") (pinfunction "2_2") (pintype "passive"))
    )
    (net (code "57") (name "Net-(Q9-G)") (class "Default")
      (node (ref "Q9") (pin "1") (pinfunction "G_1") (pintype "passive"))
      (node (ref "R75") (pin "1") (pinfunction "1_1") (pintype "passive"))
    )
    (net (code "58") (name "Net-(Q10-G)") (class "Default")
      (node (ref "D5") (pin "A") (pinfunction "A_A") (pintype "passive"))
      (node (ref "Q10") (pin "1") (pinfunction "G_1") (pintype "passive"))
      (node (ref "R89") (pin "1") (pinfunction "1_1") (pintype "passive"))
    )
    (net (code "59") (name "Net-(R50-Pad2)") (class "Default")
      (node (ref "R50") (pin "2") (pinfunction "2_2") (pintype "passive"))
      (node (ref "RJ1") (pin "Y-") (pinfunction "Y-_Y-") (pintype "bidirectional"))
    )
    (net (code "60") (name "Net-(R61-Pad2)") (class "Default")
      (node (ref "R61") (pin "2") (pinfunction "2_2") (pintype "passive"))
      (node (ref "RJ1") (pin "G-") (pinfunction "G-_G-") (pintype "bidirectional"))
    )
    (net (code "61") (name "VUSB") (class "Default")
      (node (ref "D1") (pin "A") (pinfunction "A_A") (pintype "passive"))
    )
    (net (code "62") (name "unconnected-(IC7-NC-Pad1)") (class "Default")
      (node (ref "IC7") (pin "1") (pinfunction "NC_1") (pintype "passive"))
    )
    (net (code "63") (name "unconnected-(J10-GNDBREAK-PadGND)") (class "Default")
      (node (ref "J10") (pin "GND") (pinfunction "GNDBREAK_GND") (pintype "bidirectional"))
    )
    (net (code "64") (name "unconnected-(RJ1-PadNC)") (class "Default")
      (node (ref "RJ1") (pin "NC") (pinfunction "NC_NC") (pintype "bidirectional"))
    )
  )
)
